# Main.net
KiCad netlist of a schematic drawn in Altium Designer
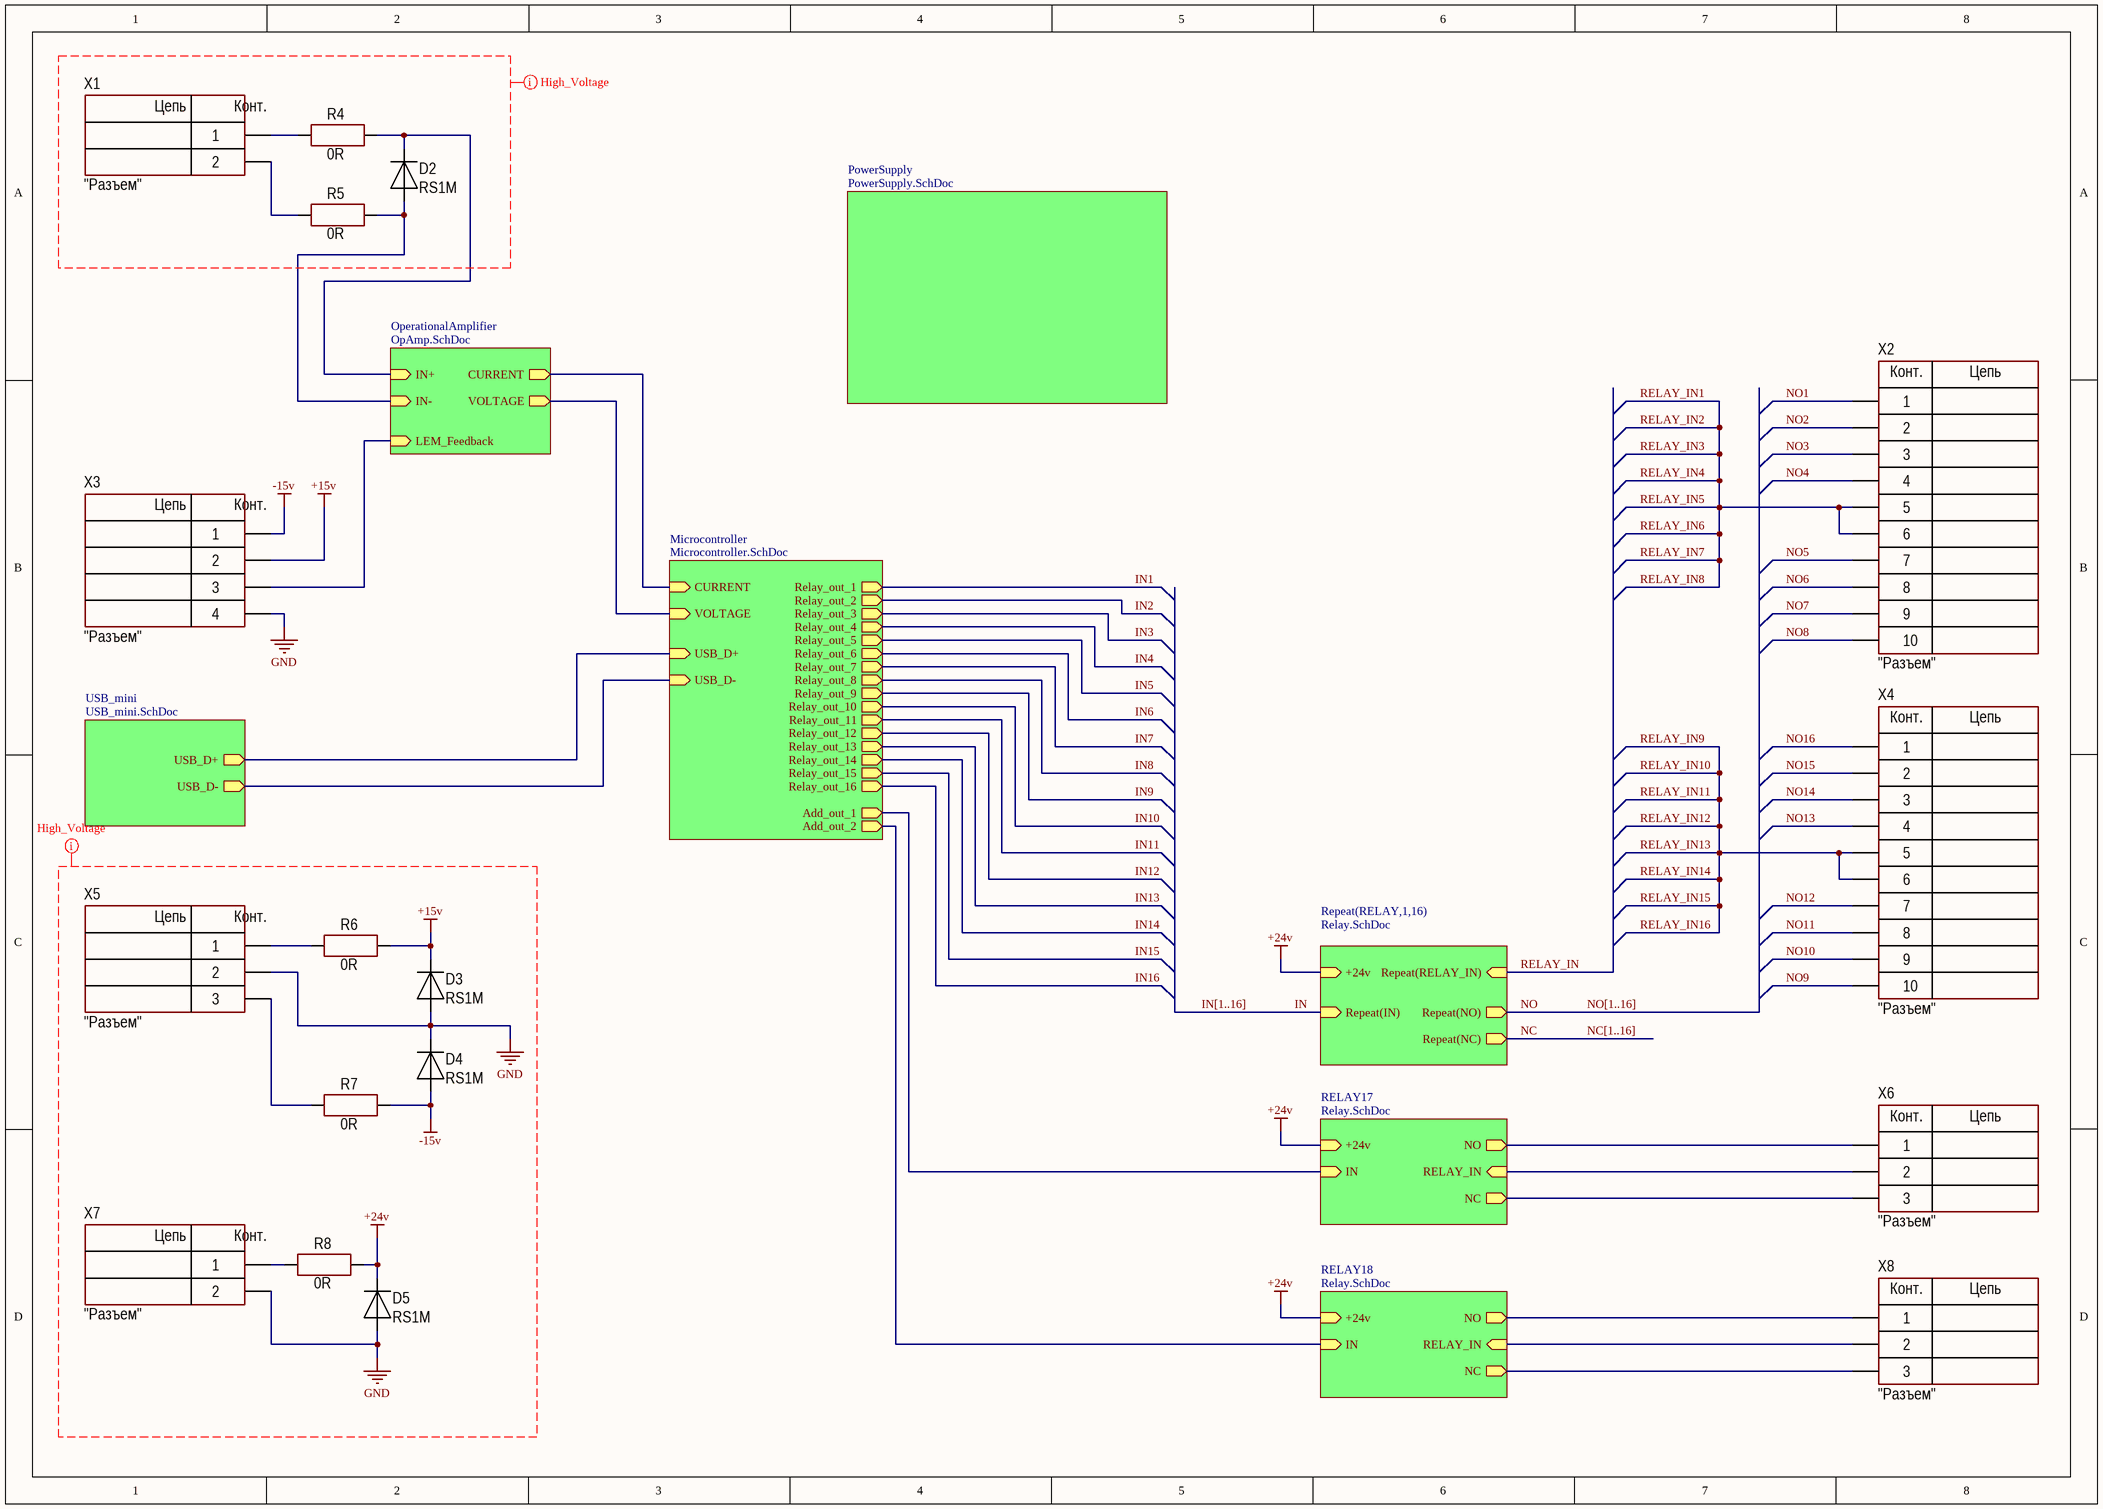
[diagram p0: Main.SchDoc]

(export (version "E")
  (design (tool "Eeschema 10.0.6"))
  (components
    (comp (ref "D2")
      (value "~")
      (footprint "StandardCase:DIODE: SMA")
      (fields
        (field (name "MANUFACTURER") "DIODES")
        (field (name "VALUEMANUFACTURERPARTNUMBER") "RS1M, SMA")
        (field (name "VOLTAGE") "1000V")
        (field (name "PARTNUMBER") "RS1M")
      )
      (libsource (lib "Diode") (part "Diode_single"))
    )
    (comp (ref "D3")
      (value "~")
      (footprint "StandardCase:DIODE: SMA")
      (fields
        (field (name "MANUFACTURER") "DIODES")
        (field (name "VALUEMANUFACTURERPARTNUMBER") "RS1M, SMA")
        (field (name "VOLTAGE") "1000V")
        (field (name "PARTNUMBER") "RS1M")
      )
      (libsource (lib "Diode") (part "Diode_single"))
    )
    (comp (ref "D4")
      (value "~")
      (footprint "StandardCase:DIODE: SMA")
      (fields
        (field (name "MANUFACTURER") "DIODES")
        (field (name "VALUEMANUFACTURERPARTNUMBER") "RS1M, SMA")
        (field (name "VOLTAGE") "1000V")
        (field (name "PARTNUMBER") "RS1M")
      )
      (libsource (lib "Diode") (part "Diode_single"))
    )
    (comp (ref "D5")
      (value "~")
      (footprint "StandardCase:DIODE: SMA")
      (fields
        (field (name "MANUFACTURER") "DIODES")
        (field (name "VALUEMANUFACTURERPARTNUMBER") "RS1M, SMA")
        (field (name "VOLTAGE") "1000V")
        (field (name "PARTNUMBER") "RS1M")
      )
      (libsource (lib "Diode") (part "Diode_single"))
    )
    (comp (ref "R4")
      (value "0R")
      (footprint "StandardCase:RES: 1206")
      (fields
        (field (name "MANUFACTURER") "Yageo")
        (field (name "PARTNUMBER") "RC1206JR-07100RL")
        (field (name "VALUEMANUFACTURERPARTNUMBER") "Resistor film, 0R, ±5%, 1206, 0.25W, -55...+125°C")
      )
      (libsource (lib "Resistor") (part "Resistor_1206"))
    )
    (comp (ref "R5")
      (value "0R")
      (footprint "StandardCase:RES: 1206")
      (fields
        (field (name "MANUFACTURER") "Yageo")
        (field (name "PARTNUMBER") "RC1206JR-07100RL")
        (field (name "VALUEMANUFACTURERPARTNUMBER") "Resistor film, 0R, ±5%, 1206, 0.25W, -55...+125°C")
      )
      (libsource (lib "Resistor") (part "Resistor_1206"))
    )
    (comp (ref "R6")
      (value "0R")
      (footprint "StandardCase:RES: 1206")
      (fields
        (field (name "MANUFACTURER") "Yageo")
        (field (name "PARTNUMBER") "RC1206JR-07100RL")
        (field (name "VALUEMANUFACTURERPARTNUMBER") "Resistor film, 0R, ±5%, 1206, 0.25W, -55...+125°C")
      )
      (libsource (lib "Resistor") (part "Resistor_1206"))
    )
    (comp (ref "R7")
      (value "0R")
      (footprint "StandardCase:RES: 1206")
      (fields
        (field (name "MANUFACTURER") "Yageo")
        (field (name "PARTNUMBER") "RC1206JR-07100RL")
        (field (name "VALUEMANUFACTURERPARTNUMBER") "Resistor film, 0R, ±5%, 1206, 0.25W, -55...+125°C")
      )
      (libsource (lib "Resistor") (part "Resistor_1206"))
    )
    (comp (ref "R8")
      (value "0R")
      (footprint "StandardCase:RES: 1206")
      (fields
        (field (name "MANUFACTURER") "Yageo")
        (field (name "PARTNUMBER") "RC1206JR-07100RL")
        (field (name "VALUEMANUFACTURERPARTNUMBER") "Resistor film, 0R, ±5%, 1206, 0.25W, -55...+125°C")
      )
      (libsource (lib "Resistor") (part "Resistor_1206"))
    )
    (comp (ref "X1")
      (value "~")
      (footprint "PcbLib1:300-021-12")
      (fields
        (field (name "MANUFACTURER") "Degson")
        (field (name "VALUEMANUFACTURERPARTNUMBER") "Terminal connector, 2pin, 3.5mm, 300VAC, 10A")
        (field (name "PARTNUMBER") "DG350-3.5-02P-14")
        (field (name "COMMENTTEXT") "\"Разъем\"")
      )
      (libsource (lib "Connector") (part "Connector_terminal_2pin"))
    )
    (comp (ref "X2")
      (value "~")
      (footprint "PcbLib1:300-101-12")
      (fields
        (field (name "MANUFACTURER") "Connfly")
        (field (name "VALUEMANUFACTURERPARTNUMBER") "Connector, 10pin, 2.54mm, 500VAC, 3A")
        (field (name "PARTNUMBER") "PLS-10")
        (field (name "COMMENTTEXT") "\"Разъем\"")
      )
      (libsource (lib "Connector") (part "PLS-10"))
    )
    (comp (ref "X3")
      (value "~")
      (footprint "PcbLib1:300-041-12")
      (fields
        (field (name "MANUFACTURER") "Connfly")
        (field (name "VALUEMANUFACTURERPARTNUMBER") "Connector, 4pin, 2.54mm, 500VAC, 3A")
        (field (name "PARTNUMBER") "PLS-4")
        (field (name "COMMENTTEXT") "\"Разъем\"")
      )
      (libsource (lib "Connector") (part "PLS-4"))
    )
    (comp (ref "X4")
      (value "~")
      (footprint "PcbLib1:300-101-12")
      (fields
        (field (name "MANUFACTURER") "Connfly")
        (field (name "VALUEMANUFACTURERPARTNUMBER") "Connector, 10pin, 2.54mm, 500VAC, 3A")
        (field (name "PARTNUMBER") "PLS-10")
        (field (name "COMMENTTEXT") "\"Разъем\"")
      )
      (libsource (lib "Connector") (part "PLS-10"))
    )
    (comp (ref "X5")
      (value "~")
      (footprint "PcbLib1:300-031-12")
      (fields
        (field (name "MANUFACTURER") "Connfly")
        (field (name "VALUEMANUFACTURERPARTNUMBER") "Connector, 3pin, 2.54mm, 500VAC, 3A")
        (field (name "PARTNUMBER") "PLS-3")
        (field (name "COMMENTTEXT") "\"Разъем\"")
      )
      (libsource (lib "Connector") (part "PLS-3"))
    )
    (comp (ref "X6")
      (value "~")
      (footprint "PcbLib1:300-031-12")
      (fields
        (field (name "MANUFACTURER") "Connfly")
        (field (name "VALUEMANUFACTURERPARTNUMBER") "Connector, 3pin, 2.54mm, 500VAC, 3A")
        (field (name "PARTNUMBER") "PLS-3")
        (field (name "COMMENTTEXT") "\"Разъем\"")
      )
      (libsource (lib "") (part "PLS-3_1"))
    )
    (comp (ref "X7")
      (value "~")
      (footprint "PcbLib1:300-021-12")
      (fields
        (field (name "MANUFACTURER") "Connfly")
        (field (name "VALUEMANUFACTURERPARTNUMBER") "Connector, 2pin, 2.54mm, 500VAC, 3A")
        (field (name "PARTNUMBER") "PLS-2")
        (field (name "COMMENTTEXT") "\"Разъем\"")
      )
      (libsource (lib "Connector") (part "PLS-2"))
    )
    (comp (ref "X8")
      (value "~")
      (footprint "PcbLib1:300-031-12")
      (fields
        (field (name "MANUFACTURER") "Connfly")
        (field (name "VALUEMANUFACTURERPARTNUMBER") "Connector, 3pin, 2.54mm, 500VAC, 3A")
        (field (name "PARTNUMBER") "PLS-3")
        (field (name "COMMENTTEXT") "\"Разъем\"")
      )
      (libsource (lib "") (part "PLS-3_1"))
    )
  )
  (nets
    (net (code "17") (name "+15v") (class "Default")
      (node (ref "D3") (pin "2") (pinfunction "2_2") (pintype "passive"))
      (node (ref "R6") (pin "1") (pinfunction "1_1") (pintype "passive"))
      (node (ref "X3") (pin "2") (pinfunction "2_2") (pintype "passive"))
    )
    (net (code "18") (name "+24v") (class "Default")
      (node (ref "D5") (pin "2") (pinfunction "2_2") (pintype "passive"))
      (node (ref "R8") (pin "1") (pinfunction "1_1") (pintype "passive"))
    )
    (net (code "19") (name "-15v") (class "Default")
      (node (ref "D4") (pin "1") (pinfunction "1_1") (pintype "passive"))
      (node (ref "R7") (pin "1") (pinfunction "1_1") (pintype "passive"))
      (node (ref "X3") (pin "1") (pinfunction "1_1") (pintype "passive"))
    )
    (net (code "24") (name "/IN+") (class "Default")
      (node (ref "D2") (pin "2") (pinfunction "2_2") (pintype "passive"))
      (node (ref "R4") (pin "1") (pinfunction "1_1") (pintype "passive"))
    )
    (net (code "25") (name "/IN-") (class "Default")
      (node (ref "D2") (pin "1") (pinfunction "1_1") (pintype "passive"))
      (node (ref "R5") (pin "1") (pinfunction "1_1") (pintype "passive"))
    )
    (net (code "43") (name "/LEM_Feedback") (class "Default")
      (node (ref "X3") (pin "3") (pinfunction "3_3") (pintype "power_in"))
    )
    (net (code "46") (name "/NC_1") (class "Default")
      (node (ref "X6") (pin "3") (pinfunction "3_3") (pintype "power_in"))
    )
    (net (code "47") (name "/NC_2") (class "Default")
      (node (ref "X8") (pin "3") (pinfunction "3_3") (pintype "power_in"))
    )
    (net (code "49") (name "/NO1") (class "Default")
      (node (ref "X2") (pin "1") (pinfunction "1_1") (pintype "passive"))
    )
    (net (code "50") (name "/NO2") (class "Default")
      (node (ref "X2") (pin "2") (pinfunction "2_2") (pintype "passive"))
    )
    (net (code "51") (name "/NO3") (class "Default")
      (node (ref "X2") (pin "3") (pinfunction "3_3") (pintype "power_in"))
    )
    (net (code "52") (name "/NO4") (class "Default")
      (node (ref "X2") (pin "4") (pinfunction "4_4") (pintype "power_in"))
    )
    (net (code "53") (name "/NO5") (class "Default")
      (node (ref "X2") (pin "7") (pinfunction "7_7") (pintype "power_in"))
    )
    (net (code "54") (name "/NO6") (class "Default")
      (node (ref "X2") (pin "8") (pinfunction "8_8") (pintype "power_in"))
    )
    (net (code "55") (name "/NO7") (class "Default")
      (node (ref "X2") (pin "9") (pinfunction "9_9") (pintype "power_in"))
    )
    (net (code "56") (name "/NO8") (class "Default")
      (node (ref "X2") (pin "10") (pinfunction "10_10") (pintype "power_in"))
    )
    (net (code "57") (name "/NO9") (class "Default")
      (node (ref "X4") (pin "10") (pinfunction "10_10") (pintype "power_in"))
    )
    (net (code "58") (name "/NO10") (class "Default")
      (node (ref "X4") (pin "9") (pinfunction "9_9") (pintype "power_in"))
    )
    (net (code "59") (name "/NO11") (class "Default")
      (node (ref "X4") (pin "8") (pinfunction "8_8") (pintype "power_in"))
    )
    (net (code "60") (name "/NO12") (class "Default")
      (node (ref "X4") (pin "7") (pinfunction "7_7") (pintype "power_in"))
    )
    (net (code "61") (name "/NO13") (class "Default")
      (node (ref "X4") (pin "4") (pinfunction "4_4") (pintype "power_in"))
    )
    (net (code "62") (name "/NO14") (class "Default")
      (node (ref "X4") (pin "3") (pinfunction "3_3") (pintype "power_in"))
    )
    (net (code "63") (name "/NO15") (class "Default")
      (node (ref "X4") (pin "2") (pinfunction "2_2") (pintype "passive"))
    )
    (net (code "64") (name "/NO16") (class "Default")
      (node (ref "X4") (pin "1") (pinfunction "1_1") (pintype "passive"))
    )
    (net (code "66") (name "/NO_1") (class "Default")
      (node (ref "X6") (pin "1") (pinfunction "1_1") (pintype "passive"))
    )
    (net (code "67") (name "/NO_2") (class "Default")
      (node (ref "X8") (pin "1") (pinfunction "1_1") (pintype "passive"))
    )
    (net (code "69") (name "/RELAY_IN1") (class "Default")
      (node (ref "X2") (pin "5") (pinfunction "5_5") (pintype "power_in"))
      (node (ref "X2") (pin "6") (pinfunction "6_6") (pintype "power_in"))
    )
    (net (code "70") (name "/RELAY_IN10") (class "Default")
      (node (ref "X4") (pin "5") (pinfunction "5_5") (pintype "power_in"))
      (node (ref "X4") (pin "6") (pinfunction "6_6") (pintype "power_in"))
    )
    (net (code "71") (name "/RELAY_IN_1") (class "Default")
      (node (ref "X6") (pin "2") (pinfunction "2_2") (pintype "passive"))
    )
    (net (code "72") (name "/RELAY_IN_2") (class "Default")
      (node (ref "X8") (pin "2") (pinfunction "2_2") (pintype "passive"))
    )
    (net (code "76") (name "GND") (class "Default")
      (node (ref "D3") (pin "1") (pinfunction "1_1") (pintype "passive"))
      (node (ref "D4") (pin "2") (pinfunction "2_2") (pintype "passive"))
      (node (ref "D5") (pin "1") (pinfunction "1_1") (pintype "passive"))
      (node (ref "X3") (pin "4") (pinfunction "4_4") (pintype "power_in"))
      (node (ref "X5") (pin "2") (pinfunction "2_2") (pintype "passive"))
      (node (ref "X7") (pin "2") (pinfunction "2_2") (pintype "passive"))
    )
    (net (code "77") (name "Net-(R4-Pad2)") (class "Default")
      (node (ref "R4") (pin "2") (pinfunction "2_2") (pintype "passive"))
      (node (ref "X1") (pin "1") (pinfunction "1_1") (pintype "passive"))
    )
    (net (code "78") (name "Net-(R5-Pad2)") (class "Default")
      (node (ref "R5") (pin "2") (pinfunction "2_2") (pintype "passive"))
      (node (ref "X1") (pin "2") (pinfunction "2_2") (pintype "passive"))
    )
    (net (code "79") (name "Net-(R6-Pad2)") (class "Default")
      (node (ref "R6") (pin "2") (pinfunction "2_2") (pintype "passive"))
      (node (ref "X5") (pin "1") (pinfunction "1_1") (pintype "passive"))
    )
    (net (code "80") (name "Net-(R7-Pad2)") (class "Default")
      (node (ref "R7") (pin "2") (pinfunction "2_2") (pintype "passive"))
      (node (ref "X5") (pin "3") (pinfunction "3_3") (pintype "power_in"))
    )
    (net (code "81") (name "Net-(R8-Pad2)") (class "Default")
      (node (ref "R8") (pin "2") (pinfunction "2_2") (pintype "passive"))
      (node (ref "X7") (pin "1") (pinfunction "1_1") (pintype "passive"))
    )
  )
)
